# Gleichrichter-Optokoppler.net
KiCad netlist of a schematic drawn in EAGLE
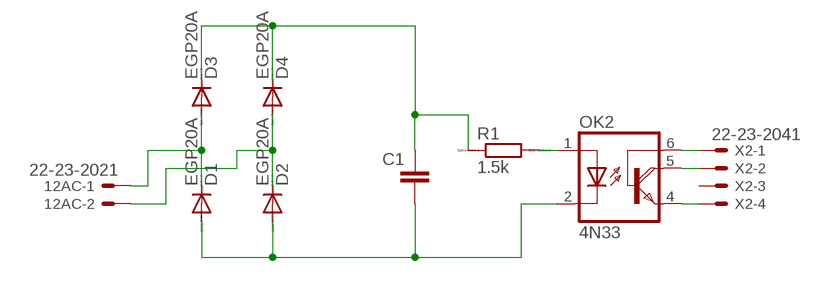
[diagram p0: schematic, sheet 1]

(export (version "E")
  (design (tool "Eeschema 10.0.6"))
  (components
    (comp (ref "12AC")
      (value "22-23-2021")
      (footprint "eagle-import:22-23-2021")
      (fields (field (name "MF") "MOLEX"))
      (libsource (lib "eagle-import") (part "22-23-2021"))
    )
    (comp (ref "C1")
      (value "C5/4.5")
      (footprint "eagle-import:C5B4.5")
      (libsource (lib "eagle-import") (part "C5/4.5"))
    )
    (comp (ref "D1")
      (value "EGP20A")
      (footprint "eagle-import:DO15-12")
      (libsource (lib "eagle-import") (part "EGP20A"))
    )
    (comp (ref "D2")
      (value "EGP20A")
      (footprint "eagle-import:DO15-12")
      (libsource (lib "eagle-import") (part "EGP20A"))
    )
    (comp (ref "D3")
      (value "EGP20A")
      (footprint "eagle-import:DO15-12")
      (libsource (lib "eagle-import") (part "EGP20A"))
    )
    (comp (ref "D4")
      (value "EGP20A")
      (footprint "eagle-import:DO15-12")
      (libsource (lib "eagle-import") (part "EGP20A"))
    )
    (comp (ref "OK2")
      (value "4N33")
      (footprint "eagle-import:DIL06")
      (fields (field (name "MF") "VISHAY/TELEFUNKEN"))
      (libsource (lib "eagle-import") (part "4N33"))
    )
    (comp (ref "R1")
      (value "1.5k")
      (footprint "eagle-import:0207_10")
      (libsource (lib "eagle-import") (part "R0207/10"))
    )
    (comp (ref "X2")
      (value "22-23-2041")
      (footprint "eagle-import:22-23-2041")
      (fields (field (name "MF") "MOLEX"))
      (libsource (lib "eagle-import") (part "22-23-2041"))
    )
  )
  (nets
    (net (code "1") (name "Net-(12ACA-S)") (class "Default")
      (node (ref "12AC") (pin "1") (pinfunction "S_1") (pintype "passive"))
      (node (ref "D1") (pin "C") (pinfunction "C_C") (pintype "passive"))
      (node (ref "D3") (pin "A") (pinfunction "A_A") (pintype "passive"))
    )
    (net (code "2") (name "Net-(12ACB-S)") (class "Default")
      (node (ref "12AC") (pin "2") (pinfunction "S_2") (pintype "passive"))
      (node (ref "D2") (pin "C") (pinfunction "C_C") (pintype "passive"))
      (node (ref "D4") (pin "A") (pinfunction "A_A") (pintype "passive"))
    )
    (net (code "3") (name "Net-(C1-Pad1)") (class "Default")
      (node (ref "C1") (pin "1") (pinfunction "1_1") (pintype "passive"))
      (node (ref "D3") (pin "C") (pinfunction "C_C") (pintype "passive"))
      (node (ref "D4") (pin "C") (pinfunction "C_C") (pintype "passive"))
      (node (ref "R1") (pin "1") (pinfunction "1_1") (pintype "passive"))
    )
    (net (code "4") (name "Net-(OK2-A)") (class "Default")
      (node (ref "OK2") (pin "1") (pinfunction "A_1") (pintype "passive"))
      (node (ref "R1") (pin "2") (pinfunction "2_2") (pintype "passive"))
    )
    (net (code "5") (name "Net-(OK2-B)") (class "Default")
      (node (ref "OK2") (pin "6") (pinfunction "B_6") (pintype "passive"))
      (node (ref "X2") (pin "1") (pinfunction "S_1") (pintype "passive"))
    )
    (net (code "6") (name "Net-(OK2-C)") (class "Default")
      (node (ref "C1") (pin "2") (pinfunction "2_2") (pintype "passive"))
      (node (ref "D1") (pin "A") (pinfunction "A_A") (pintype "passive"))
      (node (ref "D2") (pin "A") (pinfunction "A_A") (pintype "passive"))
      (node (ref "OK2") (pin "2") (pinfunction "C_2") (pintype "passive"))
    )
    (net (code "7") (name "Net-(OK2-COL)") (class "Default")
      (node (ref "OK2") (pin "5") (pinfunction "COL_5") (pintype "passive"))
      (node (ref "X2") (pin "2") (pinfunction "S_2") (pintype "passive"))
    )
    (net (code "8") (name "Net-(OK2-E)") (class "Default")
      (node (ref "OK2") (pin "4") (pinfunction "E_4") (pintype "passive"))
      (node (ref "X2") (pin "4") (pinfunction "S_4") (pintype "passive"))
    )
    (net (code "9") (name "unconnected-(X2C-S-Pad3)") (class "Default")
      (node (ref "X2") (pin "3") (pinfunction "S_3") (pintype "passive"))
    )
  )
)
